# Adafruit_FONA_SIM5320_3G_Breakout.net
KiCad netlist of a schematic drawn in EAGLE
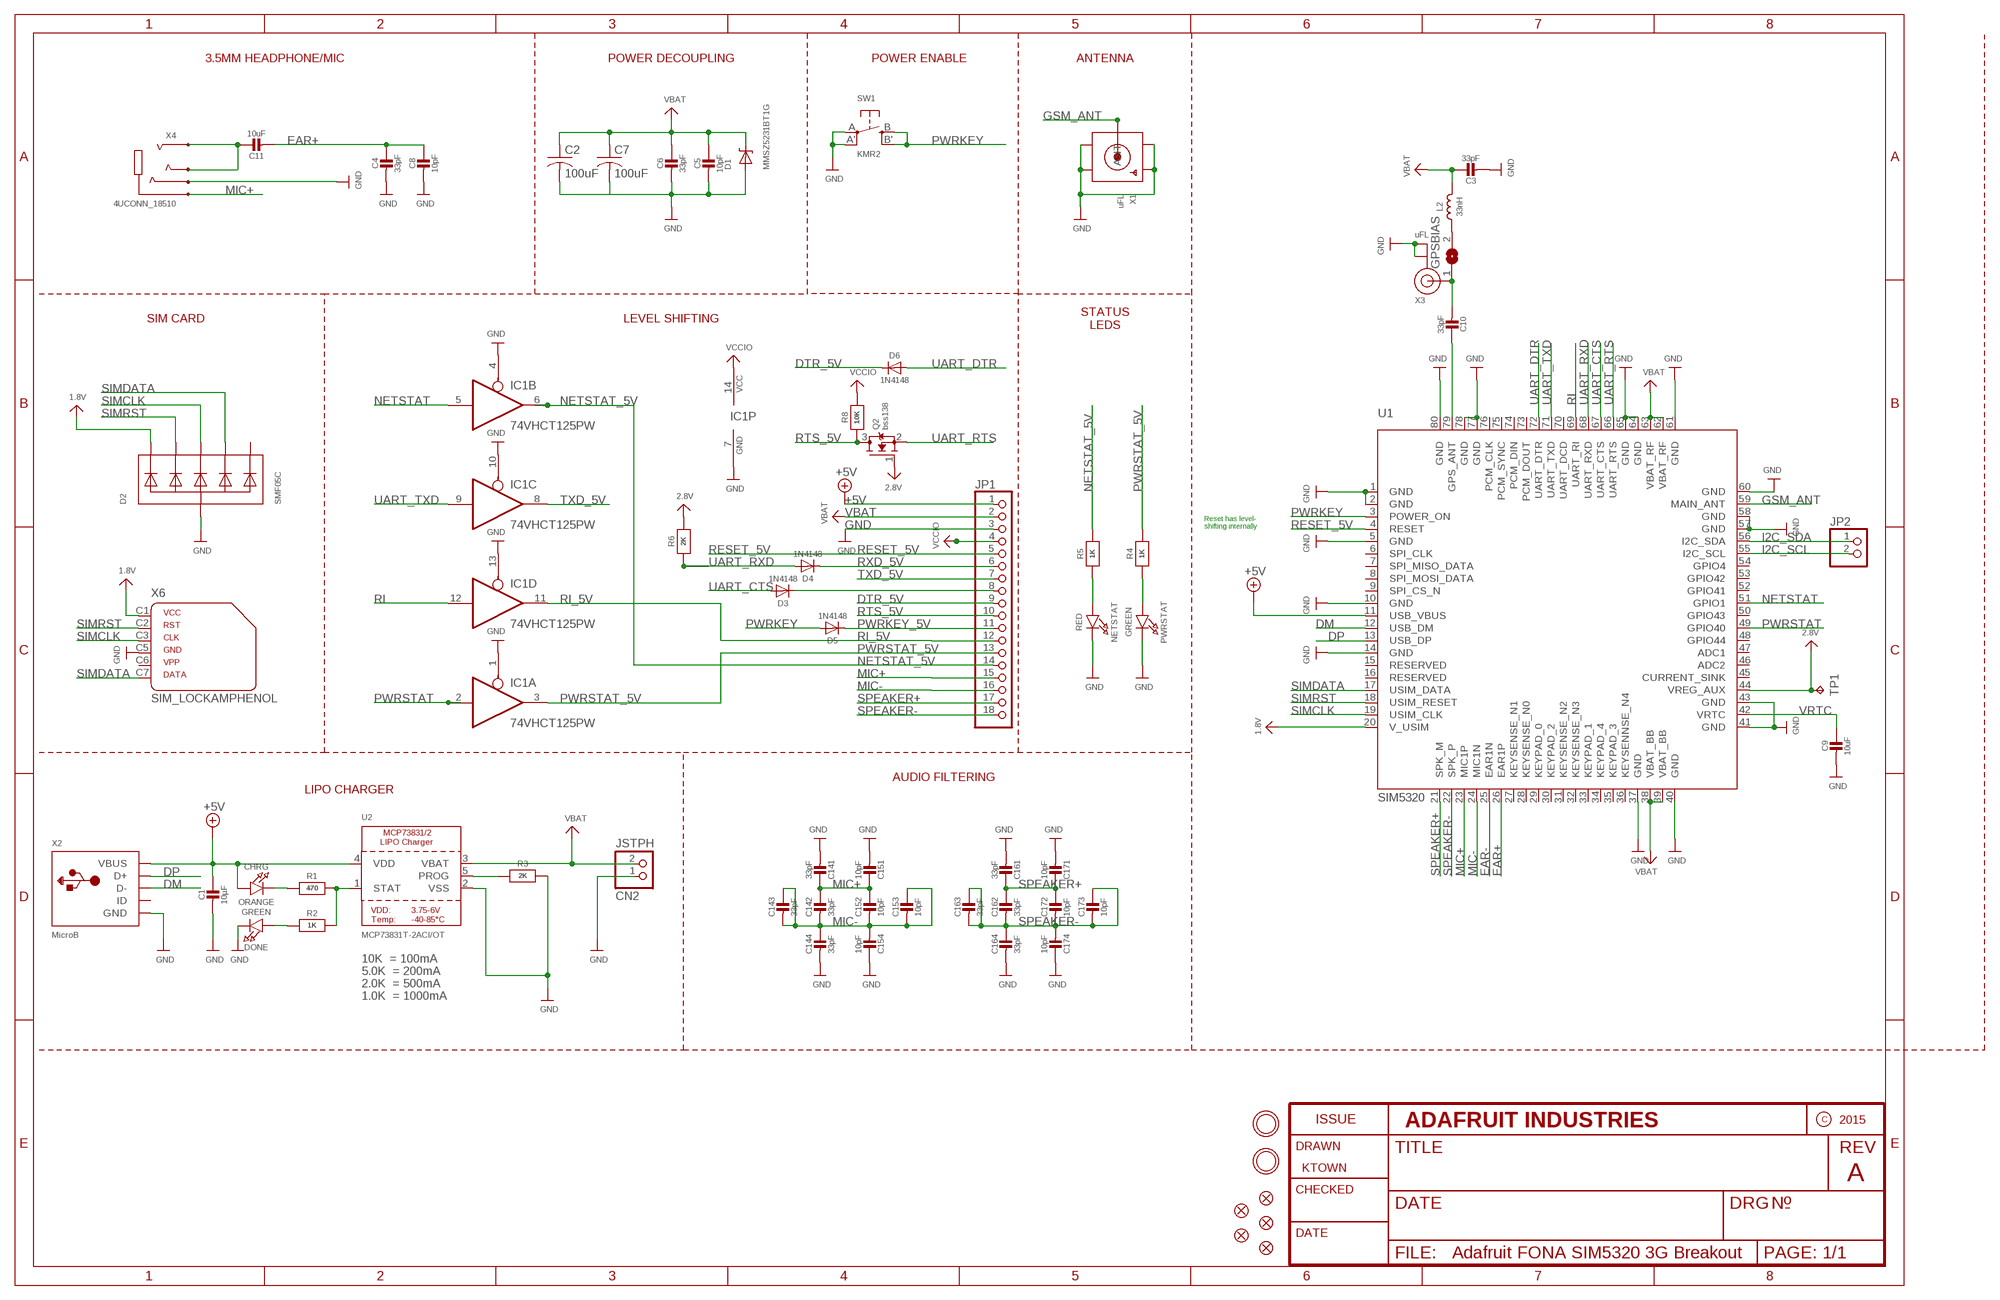
[diagram p0: schematic, sheet 1]

(export (version "E")
  (design (tool "Eeschema 10.0.6"))
  (components
    (comp (ref "C1")
      (value "10µF")
      (footprint "eagle-import:0805-NO")
      (libsource (lib "eagle-import") (part "CAP_CERAMIC0805-NOOUTLINE"))
    )
    (comp (ref "C2")
      (value "100uF")
      (footprint "eagle-import:C1210")
      (libsource (lib "eagle-import") (part "C-USC1210"))
    )
    (comp (ref "C3")
      (value "33pF")
      (footprint "eagle-import:0805-NO")
      (libsource (lib "eagle-import") (part "CAP_CERAMIC0805-NOOUTLINE"))
    )
    (comp (ref "C4")
      (value "33pF")
      (footprint "eagle-import:0805-NO")
      (libsource (lib "eagle-import") (part "CAP_CERAMIC0805-NOOUTLINE"))
    )
    (comp (ref "C5")
      (value "10pF")
      (footprint "eagle-import:0805-NO")
      (libsource (lib "eagle-import") (part "CAP_CERAMIC0805-NOOUTLINE"))
    )
    (comp (ref "C6")
      (value "33pF")
      (footprint "eagle-import:0805-NO")
      (libsource (lib "eagle-import") (part "CAP_CERAMIC0805-NOOUTLINE"))
    )
    (comp (ref "C7")
      (value "100uF")
      (footprint "eagle-import:C1210")
      (libsource (lib "eagle-import") (part "C-USC1210"))
    )
    (comp (ref "C8")
      (value "10pF")
      (footprint "eagle-import:0805-NO")
      (libsource (lib "eagle-import") (part "CAP_CERAMIC0805-NOOUTLINE"))
    )
    (comp (ref "C9")
      (value "10uF")
      (footprint "eagle-import:0805-NO")
      (libsource (lib "eagle-import") (part "CAP_CERAMIC0805-NOOUTLINE"))
    )
    (comp (ref "C10")
      (value "33pF")
      (footprint "eagle-import:0805-NO")
      (libsource (lib "eagle-import") (part "CAP_CERAMIC0805-NOOUTLINE"))
    )
    (comp (ref "C11")
      (value "10uF")
      (footprint "eagle-import:0805-NO")
      (libsource (lib "eagle-import") (part "CAP_CERAMIC0805-NOOUTLINE"))
    )
    (comp (ref "C14")
      (value "33pF")
      (footprint "eagle-import:RESPACK_4X0603")
      (libsource (lib "eagle-import") (part "CAP_4PACK1206"))
    )
    (comp (ref "C15")
      (value "10pF")
      (footprint "eagle-import:RESPACK_4X0603")
      (libsource (lib "eagle-import") (part "CAP_4PACK1206"))
    )
    (comp (ref "C16")
      (value "33pF")
      (footprint "eagle-import:RESPACK_4X0603")
      (libsource (lib "eagle-import") (part "CAP_4PACK1206"))
    )
    (comp (ref "C17")
      (value "10pF")
      (footprint "eagle-import:RESPACK_4X0603")
      (libsource (lib "eagle-import") (part "CAP_4PACK1206"))
    )
    (comp (ref "CHRG")
      (value "ORANGE")
      (footprint "eagle-import:CHIPLED_0805_NOOUTLINE")
      (libsource (lib "eagle-import") (part "LED0805_NOOUTLINE"))
    )
    (comp (ref "CN2")
      (value "JSTPH")
      (footprint "eagle-import:JSTPH2")
      (libsource (lib "eagle-import") (part "JST_2PIN"))
    )
    (comp (ref "D1")
      (value "MMSZ5231BT1G")
      (footprint "eagle-import:SOD-123")
      (libsource (lib "eagle-import") (part "DIODE-ZENERSOD123"))
    )
    (comp (ref "D2")
      (value "SMF05C")
      (footprint "eagle-import:SOT363")
      (libsource (lib "eagle-import") (part "TVSARRAY_5LANE"))
    )
    (comp (ref "D3")
      (value "1N4148")
      (footprint "eagle-import:SOD-323")
      (libsource (lib "eagle-import") (part "DIODESOD-323"))
    )
    (comp (ref "D4")
      (value "1N4148")
      (footprint "eagle-import:SOD-323")
      (libsource (lib "eagle-import") (part "DIODESOD-323"))
    )
    (comp (ref "D5")
      (value "1N4148")
      (footprint "eagle-import:SOD-323")
      (libsource (lib "eagle-import") (part "DIODESOD-323"))
    )
    (comp (ref "D6")
      (value "1N4148")
      (footprint "eagle-import:SOD-323")
      (libsource (lib "eagle-import") (part "DIODESOD-323"))
    )
    (comp (ref "DONE")
      (value "GREEN")
      (footprint "eagle-import:CHIPLED_0805_NOOUTLINE")
      (libsource (lib "eagle-import") (part "LED0805_NOOUTLINE"))
    )
    (comp (ref "FID1")
      (value "FIDUCIAL\"\"")
      (footprint "eagle-import:FIDUCIAL_1MM")
      (libsource (lib "eagle-import") (part "FIDUCIAL{dblquote}{dblquote}"))
    )
    (comp (ref "FID2")
      (value "FIDUCIAL\"\"")
      (footprint "eagle-import:FIDUCIAL_1MM")
      (libsource (lib "eagle-import") (part "FIDUCIAL{dblquote}{dblquote}"))
    )
    (comp (ref "FID3")
      (value "FIDUCIAL\"\"")
      (footprint "eagle-import:FIDUCIAL_1MM")
      (libsource (lib "eagle-import") (part "FIDUCIAL{dblquote}{dblquote}"))
    )
    (comp (ref "FID4")
      (value "FIDUCIAL\"\"")
      (footprint "eagle-import:FIDUCIAL_1MM")
      (libsource (lib "eagle-import") (part "FIDUCIAL{dblquote}{dblquote}"))
    )
    (comp (ref "FID5")
      (value "FIDUCIAL\"\"")
      (footprint "eagle-import:FIDUCIAL_1MM")
      (libsource (lib "eagle-import") (part "FIDUCIAL{dblquote}{dblquote}"))
    )
    (comp (ref "GPSBIAS")
      (value "SOLDERJUMPER")
      (footprint "eagle-import:SOLDERJUMPER_ARROW_NOPASTE")
      (libsource (lib "eagle-import") (part "SOLDERJUMPER"))
    )
    (comp (ref "IC1")
      (value "74VHCT125PW")
      (footprint "eagle-import:TSSOP14")
      (libsource (lib "eagle-import") (part "74125PWABT"))
    )
    (comp (ref "JP1")
      (value "HEADER-1X18")
      (footprint "eagle-import:1X18_ROUND70")
      (libsource (lib "eagle-import") (part "HEADER-1X18"))
    )
    (comp (ref "JP2")
      (value "HEADER-1X2ROUND")
      (footprint "eagle-import:1X02_ROUND")
      (libsource (lib "eagle-import") (part "HEADER-1X2ROUND"))
    )
    (comp (ref "L2")
      (value "33nH")
      (footprint "eagle-import:_0805MP")
      (libsource (lib "eagle-import") (part "INDUCTOR_0805MP"))
    )
    (comp (ref "NETSTAT")
      (value "RED")
      (footprint "eagle-import:CHIPLED_0805_NOOUTLINE")
      (libsource (lib "eagle-import") (part "LED0805_NOOUTLINE"))
    )
    (comp (ref "PWRSTAT")
      (value "GREEN")
      (footprint "eagle-import:CHIPLED_0805_NOOUTLINE")
      (libsource (lib "eagle-import") (part "LED0805_NOOUTLINE"))
    )
    (comp (ref "Q2")
      (value "bss138")
      (footprint "eagle-import:SOT23-WIDE")
      (libsource (lib "eagle-import") (part "MOSFET-NWIDE"))
    )
    (comp (ref "R1")
      (value "470")
      (footprint "eagle-import:0805-NO")
      (libsource (lib "eagle-import") (part "RESISTOR0805_NOOUTLINE"))
    )
    (comp (ref "R2")
      (value "1K")
      (footprint "eagle-import:0805-NO")
      (libsource (lib "eagle-import") (part "RESISTOR0805_NOOUTLINE"))
    )
    (comp (ref "R3")
      (value "2K")
      (footprint "eagle-import:0805-NO")
      (libsource (lib "eagle-import") (part "RESISTOR0805_NOOUTLINE"))
    )
    (comp (ref "R4")
      (value "1K")
      (footprint "eagle-import:0805-NO")
      (libsource (lib "eagle-import") (part "RESISTOR0805_NOOUTLINE"))
    )
    (comp (ref "R5")
      (value "1K")
      (footprint "eagle-import:0805-NO")
      (libsource (lib "eagle-import") (part "RESISTOR0805_NOOUTLINE"))
    )
    (comp (ref "R6")
      (value "2K")
      (footprint "eagle-import:0805-NO")
      (libsource (lib "eagle-import") (part "RESISTOR0805_NOOUTLINE"))
    )
    (comp (ref "R8")
      (value "10K")
      (footprint "eagle-import:0805-NO")
      (libsource (lib "eagle-import") (part "RESISTOR0805_NOOUTLINE"))
    )
    (comp (ref "SW1")
      (value "KMR2")
      (footprint "eagle-import:BTN_KMR2_4.6X2.8")
      (libsource (lib "eagle-import") (part "SWITCH_TACT_SMT4.6X2.8"))
    )
    (comp (ref "TP1")
      (value "TPTP11R")
      (footprint "eagle-import:TP11R")
      (libsource (lib "eagle-import") (part "TPTP11R"))
    )
    (comp (ref "U$33")
      (value "MOUNTINGHOLE2.5")
      (footprint "eagle-import:MOUNTINGHOLE_2.5_PLATED")
      (libsource (lib "eagle-import") (part "MOUNTINGHOLE2.5"))
    )
    (comp (ref "U$34")
      (value "MOUNTINGHOLE2.5")
      (footprint "eagle-import:MOUNTINGHOLE_2.5_PLATED")
      (libsource (lib "eagle-import") (part "MOUNTINGHOLE2.5"))
    )
    (comp (ref "U1")
      (value "SIM5320")
      (footprint "eagle-import:SIM5320")
      (libsource (lib "eagle-import") (part "GSM_SIM5320_LITERAL"))
    )
    (comp (ref "U2")
      (value "MCP73831T-2ACI/OT")
      (footprint "eagle-import:SOT23-5")
      (libsource (lib "eagle-import") (part "MCP73831/2"))
    )
    (comp (ref "X1")
      (value "uFL")
      (footprint "eagle-import:SMA_EDGELAUNCH_UFL")
      (libsource (lib "eagle-import") (part "SMACONNECTOR_EDGE_UFL"))
    )
    (comp (ref "X2")
      (value "MicroB")
      (footprint "eagle-import:4UCONN_20329")
      (libsource (lib "eagle-import") (part "USBMICRO_20329"))
    )
    (comp (ref "X3")
      (value "uFL")
      (footprint "eagle-import:U.FL")
      (libsource (lib "eagle-import") (part "ANTENNA_U.FL"))
    )
    (comp (ref "X4")
      (value "4UCONN_18510")
      (footprint "eagle-import:4UCONN_18510")
      (libsource (lib "eagle-import") (part "AUDIO_3.5MMJACK_4POL"))
    )
    (comp (ref "X6")
      (value "SIM_LOCKAMPHENOL")
      (footprint "eagle-import:C707_10M006_512_2")
      (libsource (lib "eagle-import") (part "SIM_LOCKAMPHENOL"))
    )
  )
  (nets
    (net (code "1") (name "+5V") (class "Default")
      (node (ref "C1") (pin "1") (pinfunction "1_1") (pintype "passive"))
      (node (ref "CHRG") (pin "A") (pinfunction "A_A") (pintype "passive"))
      (node (ref "JP1") (pin "1") (pinfunction "1_1") (pintype "passive"))
      (node (ref "U1") (pin "11") (pinfunction "USB_VBUS_11") (pintype "bidirectional"))
      (node (ref "U2") (pin "4") (pinfunction "VDD_4") (pintype "power_in"))
      (node (ref "X2") (pin "VBUS") (pinfunction "VBUS_VBUS") (pintype "power_in"))
    )
    (net (code "2") (name "/DM") (class "Default")
      (node (ref "U1") (pin "12") (pinfunction "USB_DM_12") (pintype "bidirectional"))
      (node (ref "X2") (pin "D-") (pinfunction "D-_D-") (pintype "bidirectional"))
    )
    (net (code "3") (name "/DP") (class "Default")
      (node (ref "U1") (pin "13") (pinfunction "USB_DP_13") (pintype "bidirectional"))
      (node (ref "X2") (pin "D+") (pinfunction "D+_D+") (pintype "bidirectional"))
    )
    (net (code "4") (name "/DTR_5V") (class "Default")
      (node (ref "D6") (pin "C") (pinfunction "C_C") (pintype "passive"))
      (node (ref "JP1") (pin "9") (pinfunction "9_9") (pintype "passive"))
    )
    (net (code "5") (name "/EAR+") (class "Default")
      (node (ref "C11") (pin "2") (pinfunction "2_2") (pintype "passive"))
      (node (ref "C4") (pin "1") (pinfunction "1_1") (pintype "passive"))
      (node (ref "C8") (pin "1") (pinfunction "1_1") (pintype "passive"))
      (node (ref "U1") (pin "26") (pinfunction "EAR1P_26") (pintype "bidirectional"))
    )
    (net (code "6") (name "/EAR-") (class "Default")
      (node (ref "U1") (pin "25") (pinfunction "EAR1N_25") (pintype "bidirectional"))
    )
    (net (code "7") (name "/GSM_ANT") (class "Default")
      (node (ref "U1") (pin "59") (pinfunction "MAIN_ANT_59") (pintype "bidirectional"))
      (node (ref "X1") (pin "P") (pinfunction "ANT_P") (pintype "bidirectional"))
    )
    (net (code "8") (name "/I2C_SCL") (class "Default")
      (node (ref "JP2") (pin "2") (pinfunction "2_2") (pintype "passive"))
      (node (ref "U1") (pin "55") (pinfunction "I2C_SCL_55") (pintype "bidirectional"))
    )
    (net (code "9") (name "/I2C_SDA") (class "Default")
      (node (ref "JP2") (pin "1") (pinfunction "1_1") (pintype "passive"))
      (node (ref "U1") (pin "56") (pinfunction "I2C_SDA_56") (pintype "bidirectional"))
    )
    (net (code "10") (name "/MIC+") (class "Default")
      (node (ref "C14") (pin "1") (pinfunction "1_1") (pintype "passive"))
      (node (ref "C14") (pin "2") (pinfunction "1_2") (pintype "passive"))
      (node (ref "C15") (pin "1") (pinfunction "1_1") (pintype "passive"))
      (node (ref "C15") (pin "2") (pinfunction "1_2") (pintype "passive"))
      (node (ref "JP1") (pin "15") (pinfunction "15_15") (pintype "passive"))
      (node (ref "U1") (pin "23") (pinfunction "MIC1P_23") (pintype "bidirectional"))
      (node (ref "X4") (pin "1-GND") (pinfunction "TIP_1-GND") (pintype "passive"))
    )
    (net (code "11") (name "/MIC-") (class "Default")
      (node (ref "C14") (pin "3") (pinfunction "1_3") (pintype "passive"))
      (node (ref "C14") (pin "4") (pinfunction "1_4") (pintype "passive"))
      (node (ref "C14") (pin "6") (pinfunction "2_6") (pintype "passive"))
      (node (ref "C14") (pin "7") (pinfunction "2_7") (pintype "passive"))
      (node (ref "C15") (pin "3") (pinfunction "1_3") (pintype "passive"))
      (node (ref "C15") (pin "5") (pinfunction "2_5") (pintype "passive"))
      (node (ref "C15") (pin "6") (pinfunction "2_6") (pintype "passive"))
      (node (ref "C15") (pin "7") (pinfunction "2_7") (pintype "passive"))
      (node (ref "JP1") (pin "16") (pinfunction "16_16") (pintype "passive"))
      (node (ref "U1") (pin "24") (pinfunction "MIC1N_24") (pintype "bidirectional"))
    )
    (net (code "12") (name "/NETSTAT") (class "Default")
      (node (ref "IC1") (pin "5") (pinfunction "I_5") (pintype "input"))
      (node (ref "U1") (pin "51") (pinfunction "GPIO1_51") (pintype "bidirectional"))
    )
    (net (code "13") (name "/NETSTAT_5V") (class "Default")
      (node (ref "IC1") (pin "6") (pinfunction "O_6") (pintype "tri_state"))
      (node (ref "JP1") (pin "14") (pinfunction "14_14") (pintype "passive"))
      (node (ref "R5") (pin "2") (pinfunction "2_2") (pintype "passive"))
    )
    (net (code "14") (name "/PWRKEY") (class "Default")
      (node (ref "D5") (pin "A") (pinfunction "A_A") (pintype "passive"))
      (node (ref "SW1") (pin "B") (pinfunction "S_B") (pintype "passive"))
      (node (ref "SW1") (pin "B'") (pinfunction "S1_B'") (pintype "passive"))
      (node (ref "U1") (pin "3") (pinfunction "POWER_ON_3") (pintype "bidirectional"))
    )
    (net (code "15") (name "/PWRKEY_5V") (class "Default")
      (node (ref "D5") (pin "C") (pinfunction "C_C") (pintype "passive"))
      (node (ref "JP1") (pin "11") (pinfunction "11_11") (pintype "passive"))
    )
    (net (code "16") (name "/PWRSTAT") (class "Default")
      (node (ref "IC1") (pin "2") (pinfunction "I_2") (pintype "input"))
      (node (ref "U1") (pin "49") (pinfunction "GPIO40_49") (pintype "bidirectional"))
    )
    (net (code "17") (name "/PWRSTAT_5V") (class "Default")
      (node (ref "IC1") (pin "3") (pinfunction "O_3") (pintype "tri_state"))
      (node (ref "JP1") (pin "13") (pinfunction "13_13") (pintype "passive"))
      (node (ref "R4") (pin "2") (pinfunction "2_2") (pintype "passive"))
    )
    (net (code "18") (name "/RESET_5V") (class "Default")
      (node (ref "JP1") (pin "5") (pinfunction "5_5") (pintype "passive"))
      (node (ref "U1") (pin "4") (pinfunction "RESET_4") (pintype "bidirectional"))
    )
    (net (code "19") (name "/RI") (class "Default")
      (node (ref "IC1") (pin "12") (pinfunction "I_12") (pintype "input"))
      (node (ref "U1") (pin "69") (pinfunction "UART_RI_69") (pintype "bidirectional"))
    )
    (net (code "20") (name "/RI_5V") (class "Default")
      (node (ref "IC1") (pin "11") (pinfunction "O_11") (pintype "tri_state"))
      (node (ref "JP1") (pin "12") (pinfunction "12_12") (pintype "passive"))
    )
    (net (code "21") (name "/RTS_5V") (class "Default")
      (node (ref "JP1") (pin "10") (pinfunction "10_10") (pintype "passive"))
      (node (ref "Q2") (pin "3") (pinfunction "D_3") (pintype "bidirectional"))
      (node (ref "R8") (pin "1") (pinfunction "1_1") (pintype "passive"))
    )
    (net (code "22") (name "/RXD_5V") (class "Default")
      (node (ref "D4") (pin "C") (pinfunction "C_C") (pintype "passive"))
      (node (ref "JP1") (pin "6") (pinfunction "6_6") (pintype "passive"))
    )
    (net (code "23") (name "/SIMCLK") (class "Default")
      (node (ref "D2") (pin "4") (pinfunction "C3_4") (pintype "passive"))
      (node (ref "U1") (pin "19") (pinfunction "USIM_CLK_19") (pintype "bidirectional"))
      (node (ref "X6") (pin "C3") (pinfunction "3_C3") (pintype "passive"))
    )
    (net (code "24") (name "/SIMDATA") (class "Default")
      (node (ref "D2") (pin "5") (pinfunction "C4_5") (pintype "passive"))
      (node (ref "U1") (pin "17") (pinfunction "USIM_DATA_17") (pintype "bidirectional"))
      (node (ref "X6") (pin "C7") (pinfunction "6_C7") (pintype "passive"))
    )
    (net (code "25") (name "/SIMRST") (class "Default")
      (node (ref "D2") (pin "3") (pinfunction "C2_3") (pintype "passive"))
      (node (ref "U1") (pin "18") (pinfunction "USIM_RESET_18") (pintype "bidirectional"))
      (node (ref "X6") (pin "C2") (pinfunction "2_C2") (pintype "passive"))
    )
    (net (code "26") (name "/SPEAKER+") (class "Default")
      (node (ref "C16") (pin "1") (pinfunction "1_1") (pintype "passive"))
      (node (ref "C16") (pin "2") (pinfunction "1_2") (pintype "passive"))
      (node (ref "C17") (pin "1") (pinfunction "1_1") (pintype "passive"))
      (node (ref "C17") (pin "2") (pinfunction "1_2") (pintype "passive"))
      (node (ref "JP1") (pin "17") (pinfunction "17_17") (pintype "passive"))
      (node (ref "U1") (pin "21") (pinfunction "SPK_M_21") (pintype "bidirectional"))
    )
    (net (code "27") (name "/SPEAKER-") (class "Default")
      (node (ref "C16") (pin "3") (pinfunction "1_3") (pintype "passive"))
      (node (ref "C16") (pin "4") (pinfunction "1_4") (pintype "passive"))
      (node (ref "C16") (pin "6") (pinfunction "2_6") (pintype "passive"))
      (node (ref "C16") (pin "7") (pinfunction "2_7") (pintype "passive"))
      (node (ref "C17") (pin "3") (pinfunction "1_3") (pintype "passive"))
      (node (ref "C17") (pin "5") (pinfunction "2_5") (pintype "passive"))
      (node (ref "C17") (pin "6") (pinfunction "2_6") (pintype "passive"))
      (node (ref "C17") (pin "7") (pinfunction "2_7") (pintype "passive"))
      (node (ref "JP1") (pin "18") (pinfunction "18_18") (pintype "passive"))
      (node (ref "U1") (pin "22") (pinfunction "SPK_P_22") (pintype "bidirectional"))
    )
    (net (code "28") (name "/TXD_5V") (class "Default")
      (node (ref "IC1") (pin "8") (pinfunction "O_8") (pintype "tri_state"))
      (node (ref "JP1") (pin "7") (pinfunction "7_7") (pintype "passive"))
    )
    (net (code "29") (name "/UART_CTS") (class "Default")
      (node (ref "D3") (pin "A") (pinfunction "A_A") (pintype "passive"))
      (node (ref "U1") (pin "67") (pinfunction "UART_CTS_67") (pintype "bidirectional"))
    )
    (net (code "30") (name "/UART_DTR") (class "Default")
      (node (ref "D6") (pin "A") (pinfunction "A_A") (pintype "passive"))
      (node (ref "U1") (pin "72") (pinfunction "UART_DTR_72") (pintype "bidirectional"))
    )
    (net (code "31") (name "/UART_RTS") (class "Default")
      (node (ref "Q2") (pin "2") (pinfunction "S_2") (pintype "bidirectional"))
      (node (ref "U1") (pin "66") (pinfunction "UART_RTS_66") (pintype "bidirectional"))
    )
    (net (code "32") (name "/UART_RXD") (class "Default")
      (node (ref "D4") (pin "A") (pinfunction "A_A") (pintype "passive"))
      (node (ref "R6") (pin "1") (pinfunction "1_1") (pintype "passive"))
      (node (ref "U1") (pin "68") (pinfunction "UART_RXD_68") (pintype "bidirectional"))
    )
    (net (code "33") (name "/UART_TXD") (class "Default")
      (node (ref "IC1") (pin "9") (pinfunction "I_9") (pintype "input"))
      (node (ref "U1") (pin "71") (pinfunction "UART_TXD_71") (pintype "bidirectional"))
    )
    (net (code "34") (name "/VRTC") (class "Default")
      (node (ref "C9") (pin "1") (pinfunction "1_1") (pintype "passive"))
      (node (ref "U1") (pin "42") (pinfunction "VRTC_42") (pintype "bidirectional"))
    )
    (net (code "35") (name "1.8V") (class "Default")
      (node (ref "D2") (pin "1") (pinfunction "C1_1") (pintype "passive"))
      (node (ref "U1") (pin "20") (pinfunction "V_USIM_20") (pintype "bidirectional"))
      (node (ref "X6") (pin "C1") (pinfunction "1_C1") (pintype "passive"))
    )
    (net (code "36") (name "2.8V") (class "Default")
      (node (ref "Q2") (pin "1") (pinfunction "G_1") (pintype "bidirectional"))
      (node (ref "R6") (pin "2") (pinfunction "2_2") (pintype "passive"))
      (node (ref "TP1") (pin "TP") (pinfunction "TP_TP") (pintype "input"))
      (node (ref "U1") (pin "44") (pinfunction "VREG_AUX_44") (pintype "bidirectional"))
    )
    (net (code "37") (name "GND") (class "Default")
      (node (ref "C1") (pin "2") (pinfunction "2_2") (pintype "passive"))
      (node (ref "C14") (pin "5") (pinfunction "2_5") (pintype "passive"))
      (node (ref "C14") (pin "8") (pinfunction "2_8") (pintype "passive"))
      (node (ref "C15") (pin "4") (pinfunction "1_4") (pintype "passive"))
      (node (ref "C15") (pin "8") (pinfunction "2_8") (pintype "passive"))
      (node (ref "C16") (pin "5") (pinfunction "2_5") (pintype "passive"))
      (node (ref "C16") (pin "8") (pinfunction "2_8") (pintype "passive"))
      (node (ref "C17") (pin "4") (pinfunction "1_4") (pintype "passive"))
      (node (ref "C17") (pin "8") (pinfunction "2_8") (pintype "passive"))
      (node (ref "C2") (pin "2") (pinfunction "2_2") (pintype "passive"))
      (node (ref "C3") (pin "2") (pinfunction "2_2") (pintype "passive"))
      (node (ref "C4") (pin "2") (pinfunction "2_2") (pintype "passive"))
      (node (ref "C5") (pin "2") (pinfunction "2_2") (pintype "passive"))
      (node (ref "C6") (pin "2") (pinfunction "2_2") (pintype "passive"))
      (node (ref "C7") (pin "2") (pinfunction "2_2") (pintype "passive"))
      (node (ref "C8") (pin "2") (pinfunction "2_2") (pintype "passive"))
      (node (ref "C9") (pin "2") (pinfunction "2_2") (pintype "passive"))
      (node (ref "CN2") (pin "1") (pinfunction "1_1") (pintype "passive"))
      (node (ref "D1") (pin "A") (pinfunction "A_A") (pintype "passive"))
      (node (ref "D2") (pin "2") (pinfunction "A_2") (pintype "passive"))
      (node (ref "DONE") (pin "C") (pinfunction "C_C") (pintype "passive"))
      (node (ref "IC1") (pin "1") (pinfunction "OE_1") (pintype "input"))
      (node (ref "IC1") (pin "10") (pinfunction "OE_10") (pintype "input"))
      (node (ref "IC1") (pin "13") (pinfunction "OE_13") (pintype "input"))
      (node (ref "IC1") (pin "4") (pinfunction "OE_4") (pintype "input"))
      (node (ref "IC1") (pin "7") (pinfunction "GND_7") (pintype "power_in"))
      (node (ref "JP1") (pin "3") (pinfunction "3_3") (pintype "passive"))
      (node (ref "NETSTAT") (pin "C") (pinfunction "C_C") (pintype "passive"))
      (node (ref "PWRSTAT") (pin "C") (pinfunction "C_C") (pintype "passive"))
      (node (ref "R3") (pin "2") (pinfunction "2_2") (pintype "passive"))
      (node (ref "SW1") (pin "A") (pinfunction "P_A") (pintype "passive"))
      (node (ref "SW1") (pin "A'") (pinfunction "P1_A'") (pintype "passive"))
      (node (ref "U1") (pin "1") (pinfunction "GND_1") (pintype "bidirectional"))
      (node (ref "U1") (pin "10") (pinfunction "GND_10") (pintype "bidirectional"))
      (node (ref "U1") (pin "14") (pinfunction "GND_14") (pintype "bidirectional"))
      (node (ref "U1") (pin "2") (pinfunction "GND_2") (pintype "bidirectional"))
      (node (ref "U1") (pin "37") (pinfunction "GND_37") (pintype "bidirectional"))
      (node (ref "U1") (pin "40") (pinfunction "GND_40") (pintype "bidirectional"))
      (node (ref "U1") (pin "41") (pinfunction "GND_41") (pintype "bidirectional"))
      (node (ref "U1") (pin "43") (pinfunction "GND_43") (pintype "bidirectional"))
      (node (ref "U1") (pin "5") (pinfunction "GND_5") (pintype "bidirectional"))
      (node (ref "U1") (pin "57") (pinfunction "GND_57") (pintype "bidirectional"))
      (node (ref "U1") (pin "58") (pinfunction "GND_58") (pintype "bidirectional"))
      (node (ref "U1") (pin "60") (pinfunction "GND_60") (pintype "bidirectional"))
      (node (ref "U1") (pin "61") (pinfunction "GND_61") (pintype "bidirectional"))
      (node (ref "U1") (pin "64") (pinfunction "GND_64") (pintype "bidirectional"))
      (node (ref "U1") (pin "65") (pinfunction "GND_65") (pintype "bidirectional"))
      (node (ref "U1") (pin "77") (pinfunction "GND_77") (pintype "bidirectional"))
      (node (ref "U1") (pin "78") (pinfunction "GND_78") (pintype "bidirectional"))
      (node (ref "U1") (pin "80") (pinfunction "GND_80") (pintype "bidirectional"))
      (node (ref "U2") (pin "2") (pinfunction "VSS_2") (pintype "power_in"))
      (node (ref "X1") (pin "GND@1") (pinfunction "GND1_GND@1") (pintype "power_in"))
      (node (ref "X1") (pin "GND@2") (pinfunction "GND2_GND@2") (pintype "power_in"))
      (node (ref "X1") (pin "GND@3") (pinfunction "GND3_GND@3") (pintype "power_in"))
      (node (ref "X1") (pin "GND@4") (pinfunction "GND4_GND@4") (pintype "power_in"))
      (node (ref "X2") (pin "BASE@1") (pinfunction "GND_BASE@1") (pintype "power_in"))
      (node (ref "X2") (pin "BASE@2") (pinfunction "GND_BASE@2") (pintype "power_in"))
      (node (ref "X2") (pin "GND") (pinfunction "GND_GND") (pintype "power_in"))
      (node (ref "X2") (pin "SPRT@1") (pinfunction "GND_SPRT@1") (pintype "power_in"))
      (node (ref "X2") (pin "SPRT@2") (pinfunction "GND_SPRT@2") (pintype "power_in"))
      (node (ref "X2") (pin "SPRT@3") (pinfunction "GND_SPRT@3") (pintype "power_in"))
      (node (ref "X2") (pin "SPRT@4") (pinfunction "GND_SPRT@4") (pintype "power_in"))
      (node (ref "X3") (pin "1") (pinfunction "GND_1") (pintype "passive"))
      (node (ref "X3") (pin "2") (pinfunction "GND_2") (pintype "passive"))
      (node (ref "X4") (pin "4-INNER_SLEEVE") (pinfunction "RING1_4-INNER_SLEEVE") (pintype "passive"))
      (node (ref "X6") (pin "C5") (pinfunction "4_C5") (pintype "passive"))
    )
    (net (code "38") (name "Net-(CHRG-PadC)") (class "Default")
      (node (ref "CHRG") (pin "C") (pinfunction "C_C") (pintype "passive"))
      (node (ref "R1") (pin "1") (pinfunction "1_1") (pintype "passive"))
    )
    (net (code "39") (name "Net-(D3-PadC)") (class "Default")
      (node (ref "D3") (pin "C") (pinfunction "C_C") (pintype "passive"))
      (node (ref "JP1") (pin "8") (pinfunction "8_8") (pintype "passive"))
    )
    (net (code "40") (name "Net-(DONE-PadA)") (class "Default")
      (node (ref "DONE") (pin "A") (pinfunction "A_A") (pintype "passive"))
      (node (ref "R2") (pin "1") (pinfunction "1_1") (pintype "passive"))
    )
    (net (code "41") (name "Net-(GPSBIAS-Pad2)") (class "Default")
      (node (ref "GPSBIAS") (pin "2") (pinfunction "2_2") (pintype "passive"))
      (node (ref "L2") (pin "1") (pinfunction "1_1") (pintype "passive"))
    )
    (net (code "42") (name "Net-(NETSTAT-PadA)") (class "Default")
      (node (ref "NETSTAT") (pin "A") (pinfunction "A_A") (pintype "passive"))
      (node (ref "R5") (pin "1") (pinfunction "1_1") (pintype "passive"))
    )
    (net (code "43") (name "Net-(PWRSTAT-PadA)") (class "Default")
      (node (ref "PWRSTAT") (pin "A") (pinfunction "A_A") (pintype "passive"))
      (node (ref "R4") (pin "1") (pinfunction "1_1") (pintype "passive"))
    )
    (net (code "44") (name "Net-(U1-GPS_ANT)") (class "Default")
      (node (ref "C10") (pin "1") (pinfunction "1_1") (pintype "passive"))
      (node (ref "U1") (pin "79") (pinfunction "GPS_ANT_79") (pintype "bidirectional"))
    )
    (net (code "45") (name "Net-(U2-PROG)") (class "Default")
      (node (ref "R3") (pin "1") (pinfunction "1_1") (pintype "passive"))
      (node (ref "U2") (pin "5") (pinfunction "PROG_5") (pintype "input"))
    )
    (net (code "46") (name "Net-(U2-STAT)") (class "Default")
      (node (ref "R1") (pin "2") (pinfunction "2_2") (pintype "passive"))
      (node (ref "R2") (pin "2") (pinfunction "2_2") (pintype "passive"))
      (node (ref "U2") (pin "1") (pinfunction "STAT_1") (pintype "output"))
    )
    (net (code "47") (name "Net-(X3-SIGNAL)") (class "Default")
      (node (ref "C10") (pin "2") (pinfunction "2_2") (pintype "passive"))
      (node (ref "GPSBIAS") (pin "1") (pinfunction "1_1") (pintype "passive"))
      (node (ref "X3") (pin "3") (pinfunction "SIGNAL_3") (pintype "passive"))
    )
    (net (code "48") (name "Net-(X4-RING2)") (class "Default")
      (node (ref "C11") (pin "1") (pinfunction "1_1") (pintype "passive"))
      (node (ref "X4") (pin "2-TIP") (pinfunction "RING3_2-TIP") (pintype "passive"))
      (node (ref "X4") (pin "3-OUTER_SLEEVE") (pinfunction "RING2_3-OUTER_SLEEVE") (pintype "passive"))
    )
    (net (code "49") (name "VBAT") (class "Default")
      (node (ref "C2") (pin "1") (pinfunction "1_1") (pintype "passive"))
      (node (ref "C3") (pin "1") (pinfunction "1_1") (pintype "passive"))
      (node (ref "C5") (pin "1") (pinfunction "1_1") (pintype "passive"))
      (node (ref "C6") (pin "1") (pinfunction "1_1") (pintype "passive"))
      (node (ref "C7") (pin "1") (pinfunction "1_1") (pintype "passive"))
      (node (ref "CN2") (pin "2") (pinfunction "2_2") (pintype "passive"))
      (node (ref "D1") (pin "C") (pinfunction "C_C") (pintype "passive"))
      (node (ref "JP1") (pin "2") (pinfunction "2_2") (pintype "passive"))
      (node (ref "L2") (pin "2") (pinfunction "2_2") (pintype "passive"))
      (node (ref "U1") (pin "38") (pinfunction "VBAT_BB_38") (pintype "bidirectional"))
      (node (ref "U1") (pin "39") (pinfunction "VBAT_BB_39") (pintype "bidirectional"))
      (node (ref "U1") (pin "62") (pinfunction "VBAT_RF_62") (pintype "bidirectional"))
      (node (ref "U1") (pin "63") (pinfunction "VBAT_RF_63") (pintype "bidirectional"))
      (node (ref "U2") (pin "3") (pinfunction "VBAT_3") (pintype "power_in"))
    )
    (net (code "50") (name "VCCIO") (class "Default")
      (node (ref "IC1") (pin "14") (pinfunction "VCC_14") (pintype "power_in"))
      (node (ref "JP1") (pin "4") (pinfunction "4_4") (pintype "passive"))
      (node (ref "R8") (pin "2") (pinfunction "2_2") (pintype "passive"))
    )
    (net (code "51") (name "unconnected-(D2-C5-Pad6)") (class "Default")
      (node (ref "D2") (pin "6") (pinfunction "C5_6") (pintype "passive"))
    )
    (net (code "52") (name "unconnected-(U1-ADC1-Pad47)") (class "Default")
      (node (ref "U1") (pin "47") (pinfunction "ADC1_47") (pintype "bidirectional"))
    )
    (net (code "53") (name "unconnected-(U1-ADC2-Pad46)") (class "Default")
      (node (ref "U1") (pin "46") (pinfunction "ADC2_46") (pintype "bidirectional"))
    )
    (net (code "54") (name "unconnected-(U1-CURRENT_SINK-Pad45)") (class "Default")
      (node (ref "U1") (pin "45") (pinfunction "CURRENT_SINK_45") (pintype "bidirectional"))
    )
    (net (code "55") (name "unconnected-(U1-GPIO4-Pad54)") (class "Default")
      (node (ref "U1") (pin "54") (pinfunction "GPIO4_54") (pintype "bidirectional"))
    )
    (net (code "56") (name "unconnected-(U1-GPIO41-Pad52)") (class "Default")
      (node (ref "U1") (pin "52") (pinfunction "GPIO41_52") (pintype "bidirectional"))
    )
    (net (code "57") (name "unconnected-(U1-GPIO42-Pad53)") (class "Default")
      (node (ref "U1") (pin "53") (pinfunction "GPIO42_53") (pintype "bidirectional"))
    )
    (net (code "58") (name "unconnected-(U1-GPIO43-Pad50)") (class "Default")
      (node (ref "U1") (pin "50") (pinfunction "GPIO43_50") (pintype "bidirectional"))
    )
    (net (code "59") (name "unconnected-(U1-GPIO44-Pad48)") (class "Default")
      (node (ref "U1") (pin "48") (pinfunction "GPIO44_48") (pintype "bidirectional"))
    )
    (net (code "60") (name "unconnected-(U1-KEYPAD_0-Pad29)") (class "Default")
      (node (ref "U1") (pin "29") (pinfunction "KEYPAD_0_29") (pintype "bidirectional"))
    )
    (net (code "61") (name "unconnected-(U1-KEYPAD_1-Pad33)") (class "Default")
      (node (ref "U1") (pin "33") (pinfunction "KEYPAD_1_33") (pintype "bidirectional"))
    )
    (net (code "62") (name "unconnected-(U1-KEYPAD_2-Pad30)") (class "Default")
      (node (ref "U1") (pin "30") (pinfunction "KEYPAD_2_30") (pintype "bidirectional"))
    )
    (net (code "63") (name "unconnected-(U1-KEYPAD_3-Pad35)") (class "Default")
      (node (ref "U1") (pin "35") (pinfunction "KEYPAD_3_35") (pintype "bidirectional"))
    )
    (net (code "64") (name "unconnected-(U1-KEYPAD_4-Pad34)") (class "Default")
      (node (ref "U1") (pin "34") (pinfunction "KEYPAD_4_34") (pintype "bidirectional"))
    )
    (net (code "65") (name "unconnected-(U1-KEYSENNSE_N4-Pad36)") (class "Default")
      (node (ref "U1") (pin "36") (pinfunction "KEYSENNSE_N4_36") (pintype "bidirectional"))
    )
    (net (code "66") (name "unconnected-(U1-KEYSENSE_N0-Pad28)") (class "Default")
      (node (ref "U1") (pin "28") (pinfunction "KEYSENSE_N0_28") (pintype "bidirectional"))
    )
    (net (code "67") (name "unconnected-(U1-KEYSENSE_N1-Pad27)") (class "Default")
      (node (ref "U1") (pin "27") (pinfunction "KEYSENSE_N1_27") (pintype "bidirectional"))
    )
    (net (code "68") (name "unconnected-(U1-KEYSENSE_N2-Pad31)") (class "Default")
      (node (ref "U1") (pin "31") (pinfunction "KEYSENSE_N2_31") (pintype "bidirectional"))
    )
    (net (code "69") (name "unconnected-(U1-KEYSENSE_N3-Pad32)") (class "Default")
      (node (ref "U1") (pin "32") (pinfunction "KEYSENSE_N3_32") (pintype "bidirectional"))
    )
    (net (code "70") (name "unconnected-(U1-PCM_CLK-Pad76)") (class "Default")
      (node (ref "U1") (pin "76") (pinfunction "PCM_CLK_76") (pintype "bidirectional"))
    )
    (net (code "71") (name "unconnected-(U1-PCM_DIN-Pad74)") (class "Default")
      (node (ref "U1") (pin "74") (pinfunction "PCM_DIN_74") (pintype "bidirectional"))
    )
    (net (code "72") (name "unconnected-(U1-PCM_DOUT-Pad73)") (class "Default")
      (node (ref "U1") (pin "73") (pinfunction "PCM_DOUT_73") (pintype "bidirectional"))
    )
    (net (code "73") (name "unconnected-(U1-PCM_SYNC-Pad75)") (class "Default")
      (node (ref "U1") (pin "75") (pinfunction "PCM_SYNC_75") (pintype "bidirectional"))
    )
    (net (code "74") (name "unconnected-(U1-RESERVED-Pad15)") (class "Default")
      (node (ref "U1") (pin "15") (pinfunction "RESERVED_15") (pintype "bidirectional"))
    )
    (net (code "75") (name "unconnected-(U1-RESERVED-Pad16)") (class "Default")
      (node (ref "U1") (pin "16") (pinfunction "RESERVED_16") (pintype "bidirectional"))
    )
    (net (code "76") (name "unconnected-(U1-SPI_CLK-Pad6)") (class "Default")
      (node (ref "U1") (pin "6") (pinfunction "SPI_CLK_6") (pintype "bidirectional"))
    )
    (net (code "77") (name "unconnected-(U1-SPI_CS_N-Pad9)") (class "Default")
      (node (ref "U1") (pin "9") (pinfunction "SPI_CS_N_9") (pintype "bidirectional"))
    )
    (net (code "78") (name "unconnected-(U1-SPI_MISO_DATA-Pad7)") (class "Default")
      (node (ref "U1") (pin "7") (pinfunction "SPI_MISO_DATA_7") (pintype "bidirectional"))
    )
    (net (code "79") (name "unconnected-(U1-SPI_MOSI_DATA-Pad8)") (class "Default")
      (node (ref "U1") (pin "8") (pinfunction "SPI_MOSI_DATA_8") (pintype "bidirectional"))
    )
    (net (code "80") (name "unconnected-(U1-UART_DCD-Pad70)") (class "Default")
      (node (ref "U1") (pin "70") (pinfunction "UART_DCD_70") (pintype "bidirectional"))
    )
    (net (code "81") (name "unconnected-(X2-PadID)") (class "Default")
      (node (ref "X2") (pin "ID") (pinfunction "ID_ID") (pintype "bidirectional"))
    )
    (net (code "82") (name "unconnected-(X6-5-PadC6)") (class "Default")
      (node (ref "X6") (pin "C6") (pinfunction "5_C6") (pintype "passive"))
    )
  )
)
